# control_board.net
KiCad netlist of a schematic drawn in EAGLE
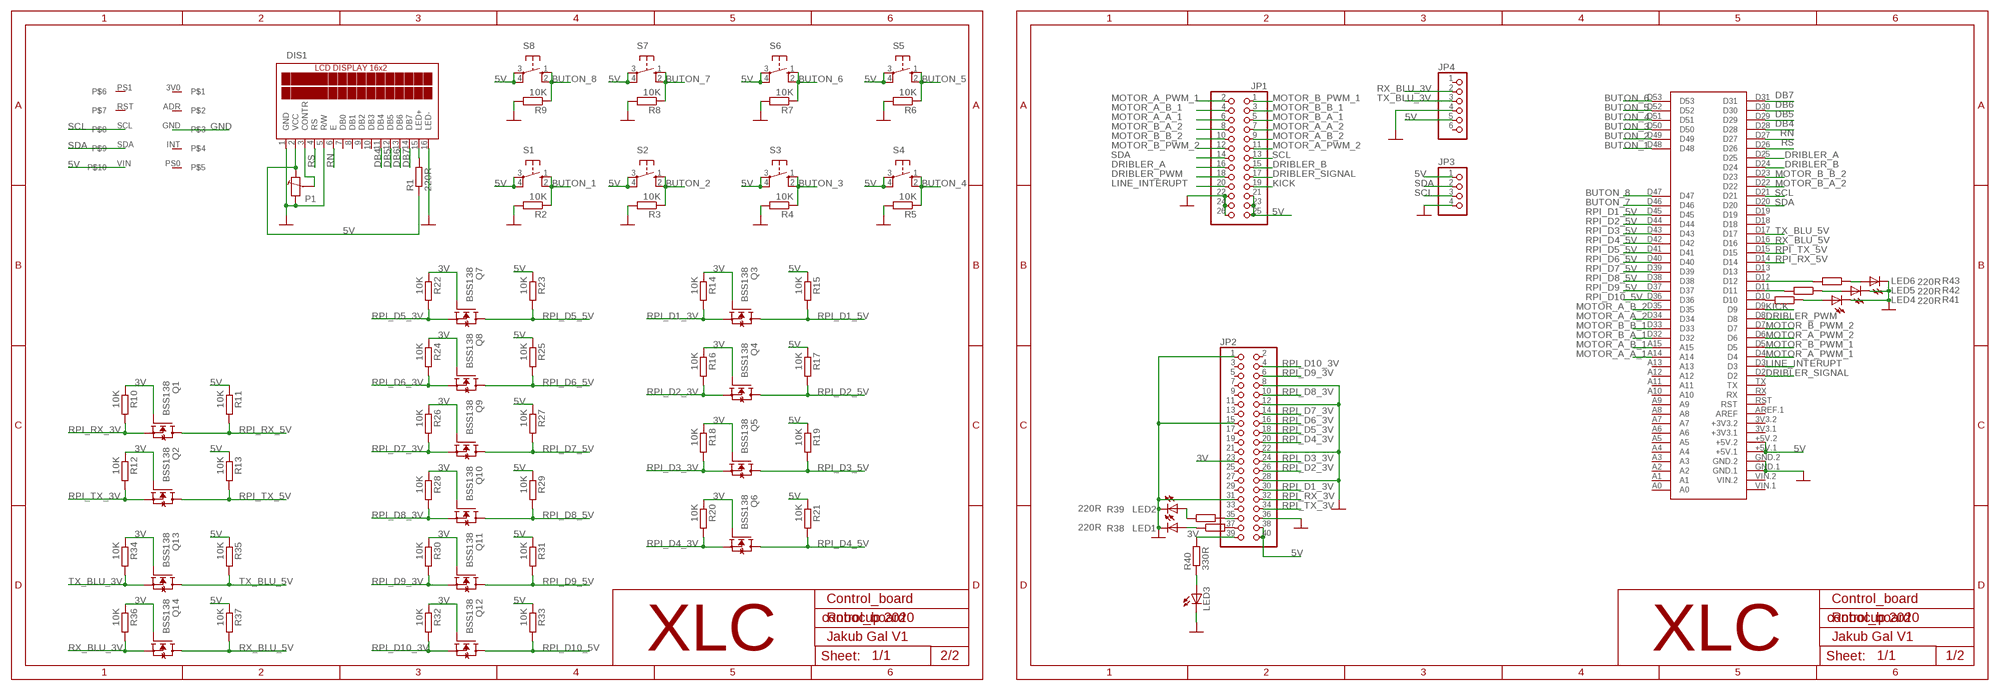
[diagram p0: schematic, sheet 1]

(export (version "E")
  (design (tool "Eeschema 10.0.6"))
  (components
    (comp (ref "DIS1")
      (value "LCD_DISPLEJ_16X2Z")
      (footprint "eagle-import:LCD_DISPLEJ_16X2")
      (libsource (lib "eagle-import") (part "LCD_DISPLEJ_16X2Z"))
    )
    (comp (ref "JP1")
      (value "PINHD-2X13_2.54")
      (footprint "eagle-import:2X13")
      (libsource (lib "eagle-import") (part "PINHD-2X13_2.54"))
    )
    (comp (ref "JP2")
      (value "PINHD-2X20_2.54")
      (footprint "eagle-import:2X20")
      (libsource (lib "eagle-import") (part "PINHD-2X20_2.54"))
    )
    (comp (ref "JP3")
      (value "PINHD-1X4_2.54")
      (footprint "eagle-import:1X04")
      (libsource (lib "eagle-import") (part "PINHD-1X4_2.54"))
    )
    (comp (ref "JP4")
      (value "PINHD-1X6_2.54")
      (footprint "eagle-import:1X06")
      (libsource (lib "eagle-import") (part "PINHD-1X6_2.54"))
    )
    (comp (ref "LED1")
      (value "LEDCHIPLED_0603")
      (footprint "eagle-import:CHIPLED_0603")
      (libsource (lib "eagle-import") (part "LEDCHIPLED_0603"))
    )
    (comp (ref "LED2")
      (value "LEDCHIPLED_0603")
      (footprint "eagle-import:CHIPLED_0603")
      (libsource (lib "eagle-import") (part "LEDCHIPLED_0603"))
    )
    (comp (ref "LED3")
      (value "LEDCHIPLED_0603")
      (footprint "eagle-import:CHIPLED_0603")
      (libsource (lib "eagle-import") (part "LEDCHIPLED_0603"))
    )
    (comp (ref "LED4")
      (value "LEDCHIPLED_0603")
      (footprint "eagle-import:CHIPLED_0603")
      (libsource (lib "eagle-import") (part "LEDCHIPLED_0603"))
    )
    (comp (ref "LED5")
      (value "LEDCHIPLED_0603")
      (footprint "eagle-import:CHIPLED_0603")
      (libsource (lib "eagle-import") (part "LEDCHIPLED_0603"))
    )
    (comp (ref "LED6")
      (value "LEDCHIPLED_0603")
      (footprint "eagle-import:CHIPLED_0603")
      (libsource (lib "eagle-import") (part "LEDCHIPLED_0603"))
    )
    (comp (ref "P1")
      (value "TRIMER-CA6V")
      (footprint "eagle-import:TP-CA6V")
      (libsource (lib "eagle-import") (part "TRIMER-CA6V"))
    )
    (comp (ref "Q1")
      (value "BSS138")
      (footprint "eagle-import:SOT23")
      (fields (field (name "MF") "Fairchild"))
      (libsource (lib "eagle-import") (part "BSS138"))
    )
    (comp (ref "Q2")
      (value "BSS138")
      (footprint "eagle-import:SOT23")
      (fields (field (name "MF") "Fairchild"))
      (libsource (lib "eagle-import") (part "BSS138"))
    )
    (comp (ref "Q3")
      (value "BSS138")
      (footprint "eagle-import:SOT23")
      (fields (field (name "MF") "Fairchild"))
      (libsource (lib "eagle-import") (part "BSS138"))
    )
    (comp (ref "Q4")
      (value "BSS138")
      (footprint "eagle-import:SOT23")
      (fields (field (name "MF") "Fairchild"))
      (libsource (lib "eagle-import") (part "BSS138"))
    )
    (comp (ref "Q5")
      (value "BSS138")
      (footprint "eagle-import:SOT23")
      (fields (field (name "MF") "Fairchild"))
      (libsource (lib "eagle-import") (part "BSS138"))
    )
    (comp (ref "Q6")
      (value "BSS138")
      (footprint "eagle-import:SOT23")
      (fields (field (name "MF") "Fairchild"))
      (libsource (lib "eagle-import") (part "BSS138"))
    )
    (comp (ref "Q7")
      (value "BSS138")
      (footprint "eagle-import:SOT23")
      (fields (field (name "MF") "Fairchild"))
      (libsource (lib "eagle-import") (part "BSS138"))
    )
    (comp (ref "Q8")
      (value "BSS138")
      (footprint "eagle-import:SOT23")
      (fields (field (name "MF") "Fairchild"))
      (libsource (lib "eagle-import") (part "BSS138"))
    )
    (comp (ref "Q9")
      (value "BSS138")
      (footprint "eagle-import:SOT23")
      (fields (field (name "MF") "Fairchild"))
      (libsource (lib "eagle-import") (part "BSS138"))
    )
    (comp (ref "Q10")
      (value "BSS138")
      (footprint "eagle-import:SOT23")
      (fields (field (name "MF") "Fairchild"))
      (libsource (lib "eagle-import") (part "BSS138"))
    )
    (comp (ref "Q11")
      (value "BSS138")
      (footprint "eagle-import:SOT23")
      (fields (field (name "MF") "Fairchild"))
      (libsource (lib "eagle-import") (part "BSS138"))
    )
    (comp (ref "Q12")
      (value "BSS138")
      (footprint "eagle-import:SOT23")
      (fields (field (name "MF") "Fairchild"))
      (libsource (lib "eagle-import") (part "BSS138"))
    )
    (comp (ref "Q13")
      (value "BSS138")
      (footprint "eagle-import:SOT23")
      (fields (field (name "MF") "Fairchild"))
      (libsource (lib "eagle-import") (part "BSS138"))
    )
    (comp (ref "Q14")
      (value "BSS138")
      (footprint "eagle-import:SOT23")
      (fields (field (name "MF") "Fairchild"))
      (libsource (lib "eagle-import") (part "BSS138"))
    )
    (comp (ref "R1")
      (value "220R")
      (footprint "eagle-import:R0603")
      (libsource (lib "eagle-import") (part "R-EU_R0603"))
    )
    (comp (ref "R2")
      (value "10K")
      (footprint "eagle-import:R0603")
      (libsource (lib "eagle-import") (part "R-EU_R0603"))
    )
    (comp (ref "R3")
      (value "10K")
      (footprint "eagle-import:R0603")
      (libsource (lib "eagle-import") (part "R-EU_R0603"))
    )
    (comp (ref "R4")
      (value "10K")
      (footprint "eagle-import:R0603")
      (libsource (lib "eagle-import") (part "R-EU_R0603"))
    )
    (comp (ref "R5")
      (value "10K")
      (footprint "eagle-import:R0603")
      (libsource (lib "eagle-import") (part "R-EU_R0603"))
    )
    (comp (ref "R6")
      (value "10K")
      (footprint "eagle-import:R0603")
      (libsource (lib "eagle-import") (part "R-EU_R0603"))
    )
    (comp (ref "R7")
      (value "10K")
      (footprint "eagle-import:R0603")
      (libsource (lib "eagle-import") (part "R-EU_R0603"))
    )
    (comp (ref "R8")
      (value "10K")
      (footprint "eagle-import:R0603")
      (libsource (lib "eagle-import") (part "R-EU_R0603"))
    )
    (comp (ref "R9")
      (value "10K")
      (footprint "eagle-import:R0603")
      (libsource (lib "eagle-import") (part "R-EU_R0603"))
    )
    (comp (ref "R10")
      (value "10K")
      (footprint "eagle-import:R0603")
      (libsource (lib "eagle-import") (part "R-EU_R0603"))
    )
    (comp (ref "R11")
      (value "10K")
      (footprint "eagle-import:R0603")
      (libsource (lib "eagle-import") (part "R-EU_R0603"))
    )
    (comp (ref "R12")
      (value "10K")
      (footprint "eagle-import:R0603")
      (libsource (lib "eagle-import") (part "R-EU_R0603"))
    )
    (comp (ref "R13")
      (value "10K")
      (footprint "eagle-import:R0603")
      (libsource (lib "eagle-import") (part "R-EU_R0603"))
    )
    (comp (ref "R14")
      (value "10K")
      (footprint "eagle-import:R0603")
      (libsource (lib "eagle-import") (part "R-EU_R0603"))
    )
    (comp (ref "R15")
      (value "10K")
      (footprint "eagle-import:R0603")
      (libsource (lib "eagle-import") (part "R-EU_R0603"))
    )
    (comp (ref "R16")
      (value "10K")
      (footprint "eagle-import:R0603")
      (libsource (lib "eagle-import") (part "R-EU_R0603"))
    )
    (comp (ref "R17")
      (value "10K")
      (footprint "eagle-import:R0603")
      (libsource (lib "eagle-import") (part "R-EU_R0603"))
    )
    (comp (ref "R18")
      (value "10K")
      (footprint "eagle-import:R0603")
      (libsource (lib "eagle-import") (part "R-EU_R0603"))
    )
    (comp (ref "R19")
      (value "10K")
      (footprint "eagle-import:R0603")
      (libsource (lib "eagle-import") (part "R-EU_R0603"))
    )
    (comp (ref "R20")
      (value "10K")
      (footprint "eagle-import:R0603")
      (libsource (lib "eagle-import") (part "R-EU_R0603"))
    )
    (comp (ref "R21")
      (value "10K")
      (footprint "eagle-import:R0603")
      (libsource (lib "eagle-import") (part "R-EU_R0603"))
    )
    (comp (ref "R22")
      (value "10K")
      (footprint "eagle-import:R0603")
      (libsource (lib "eagle-import") (part "R-EU_R0603"))
    )
    (comp (ref "R23")
      (value "10K")
      (footprint "eagle-import:R0603")
      (libsource (lib "eagle-import") (part "R-EU_R0603"))
    )
    (comp (ref "R24")
      (value "10K")
      (footprint "eagle-import:R0603")
      (libsource (lib "eagle-import") (part "R-EU_R0603"))
    )
    (comp (ref "R25")
      (value "10K")
      (footprint "eagle-import:R0603")
      (libsource (lib "eagle-import") (part "R-EU_R0603"))
    )
    (comp (ref "R26")
      (value "10K")
      (footprint "eagle-import:R0603")
      (libsource (lib "eagle-import") (part "R-EU_R0603"))
    )
    (comp (ref "R27")
      (value "10K")
      (footprint "eagle-import:R0603")
      (libsource (lib "eagle-import") (part "R-EU_R0603"))
    )
    (comp (ref "R28")
      (value "10K")
      (footprint "eagle-import:R0603")
      (libsource (lib "eagle-import") (part "R-EU_R0603"))
    )
    (comp (ref "R29")
      (value "10K")
      (footprint "eagle-import:R0603")
      (libsource (lib "eagle-import") (part "R-EU_R0603"))
    )
    (comp (ref "R30")
      (value "10K")
      (footprint "eagle-import:R0603")
      (libsource (lib "eagle-import") (part "R-EU_R0603"))
    )
    (comp (ref "R31")
      (value "10K")
      (footprint "eagle-import:R0603")
      (libsource (lib "eagle-import") (part "R-EU_R0603"))
    )
    (comp (ref "R32")
      (value "10K")
      (footprint "eagle-import:R0603")
      (libsource (lib "eagle-import") (part "R-EU_R0603"))
    )
    (comp (ref "R33")
      (value "10K")
      (footprint "eagle-import:R0603")
      (libsource (lib "eagle-import") (part "R-EU_R0603"))
    )
    (comp (ref "R34")
      (value "10K")
      (footprint "eagle-import:R0603")
      (libsource (lib "eagle-import") (part "R-EU_R0603"))
    )
    (comp (ref "R35")
      (value "10K")
      (footprint "eagle-import:R0603")
      (libsource (lib "eagle-import") (part "R-EU_R0603"))
    )
    (comp (ref "R36")
      (value "10K")
      (footprint "eagle-import:R0603")
      (libsource (lib "eagle-import") (part "R-EU_R0603"))
    )
    (comp (ref "R37")
      (value "10K")
      (footprint "eagle-import:R0603")
      (libsource (lib "eagle-import") (part "R-EU_R0603"))
    )
    (comp (ref "R38")
      (value "220R")
      (footprint "eagle-import:R0603")
      (libsource (lib "eagle-import") (part "R-EU_R0603"))
    )
    (comp (ref "R39")
      (value "220R")
      (footprint "eagle-import:R0603")
      (libsource (lib "eagle-import") (part "R-EU_R0603"))
    )
    (comp (ref "R40")
      (value "330R")
      (footprint "eagle-import:R0603")
      (libsource (lib "eagle-import") (part "R-EU_R0603"))
    )
    (comp (ref "R41")
      (value "220R")
      (footprint "eagle-import:R0603")
      (libsource (lib "eagle-import") (part "R-EU_R0603"))
    )
    (comp (ref "R42")
      (value "220R")
      (footprint "eagle-import:R0603")
      (libsource (lib "eagle-import") (part "R-EU_R0603"))
    )
    (comp (ref "R43")
      (value "220R")
      (footprint "eagle-import:R0603")
      (libsource (lib "eagle-import") (part "R-EU_R0603"))
    )
    (comp (ref "S1")
      (value "10-XX")
      (footprint "eagle-import:B3F-10XX")
      (fields (field (name "MPN") "B3F-1000"))
      (libsource (lib "eagle-import") (part "10-XX"))
    )
    (comp (ref "S2")
      (value "10-XX")
      (footprint "eagle-import:B3F-10XX")
      (fields (field (name "MPN") "B3F-1000"))
      (libsource (lib "eagle-import") (part "10-XX"))
    )
    (comp (ref "S3")
      (value "10-XX")
      (footprint "eagle-import:B3F-10XX")
      (fields (field (name "MPN") "B3F-1000"))
      (libsource (lib "eagle-import") (part "10-XX"))
    )
    (comp (ref "S4")
      (value "10-XX")
      (footprint "eagle-import:B3F-10XX")
      (fields (field (name "MPN") "B3F-1000"))
      (libsource (lib "eagle-import") (part "10-XX"))
    )
    (comp (ref "S5")
      (value "10-XX")
      (footprint "eagle-import:B3F-10XX")
      (fields (field (name "MPN") "B3F-1000"))
      (libsource (lib "eagle-import") (part "10-XX"))
    )
    (comp (ref "S6")
      (value "10-XX")
      (footprint "eagle-import:B3F-10XX")
      (fields (field (name "MPN") "B3F-1000"))
      (libsource (lib "eagle-import") (part "10-XX"))
    )
    (comp (ref "S7")
      (value "10-XX")
      (footprint "eagle-import:B3F-10XX")
      (fields (field (name "MPN") "B3F-1000"))
      (libsource (lib "eagle-import") (part "10-XX"))
    )
    (comp (ref "S8")
      (value "10-XX")
      (footprint "eagle-import:B3F-10XX")
      (fields (field (name "MPN") "B3F-1000"))
      (libsource (lib "eagle-import") (part "10-XX"))
    )
    (comp (ref "U$1")
      (value "MEGA2560_MIKRO")
      (footprint "eagle-import:MEGA2560_MIKRO")
      (libsource (lib "eagle-import") (part "MEGA2560_MIKRO"))
    )
    (comp (ref "U$2")
      (value "BNO055")
      (footprint "eagle-import:BNO005")
      (libsource (lib "eagle-import") (part "BNO055"))
    )
  )
  (nets
    (net (code "1") (name "/3V") (class "Default")
      (node (ref "JP2") (pin "23") (pinfunction "23_23") (pintype "passive"))
      (node (ref "JP2") (pin "39") (pinfunction "39_39") (pintype "passive"))
      (node (ref "Q1") (pin "1") (pinfunction "G_1") (pintype "passive"))
      (node (ref "Q10") (pin "1") (pinfunction "G_1") (pintype "passive"))
      (node (ref "Q11") (pin "1") (pinfunction "G_1") (pintype "passive"))
      (node (ref "Q12") (pin "1") (pinfunction "G_1") (pintype "passive"))
      (node (ref "Q13") (pin "1") (pinfunction "G_1") (pintype "passive"))
      (node (ref "Q14") (pin "1") (pinfunction "G_1") (pintype "passive"))
      (node (ref "Q2") (pin "1") (pinfunction "G_1") (pintype "passive"))
      (node (ref "Q3") (pin "1") (pinfunction "G_1") (pintype "passive"))
      (node (ref "Q4") (pin "1") (pinfunction "G_1") (pintype "passive"))
      (node (ref "Q5") (pin "1") (pinfunction "G_1") (pintype "passive"))
      (node (ref "Q6") (pin "1") (pinfunction "G_1") (pintype "passive"))
      (node (ref "Q7") (pin "1") (pinfunction "G_1") (pintype "passive"))
      (node (ref "Q8") (pin "1") (pinfunction "G_1") (pintype "passive"))
      (node (ref "Q9") (pin "1") (pinfunction "G_1") (pintype "passive"))
      (node (ref "R10") (pin "1") (pinfunction "1_1") (pintype "passive"))
      (node (ref "R12") (pin "1") (pinfunction "1_1") (pintype "passive"))
      (node (ref "R14") (pin "1") (pinfunction "1_1") (pintype "passive"))
      (node (ref "R16") (pin "1") (pinfunction "1_1") (pintype "passive"))
      (node (ref "R18") (pin "1") (pinfunction "1_1") (pintype "passive"))
      (node (ref "R20") (pin "1") (pinfunction "1_1") (pintype "passive"))
      (node (ref "R22") (pin "1") (pinfunction "1_1") (pintype "passive"))
      (node (ref "R24") (pin "1") (pinfunction "1_1") (pintype "passive"))
      (node (ref "R26") (pin "1") (pinfunction "1_1") (pintype "passive"))
      (node (ref "R28") (pin "1") (pinfunction "1_1") (pintype "passive"))
      (node (ref "R30") (pin "1") (pinfunction "1_1") (pintype "passive"))
      (node (ref "R32") (pin "1") (pinfunction "1_1") (pintype "passive"))
      (node (ref "R34") (pin "1") (pinfunction "1_1") (pintype "passive"))
      (node (ref "R36") (pin "1") (pinfunction "1_1") (pintype "passive"))
      (node (ref "R40") (pin "2") (pinfunction "2_2") (pintype "passive"))
    )
    (net (code "2") (name "/5V") (class "Default")
      (node (ref "DIS1") (pin "2") (pinfunction "VCC_2") (pintype "power_in"))
      (node (ref "JP1") (pin "21") (pinfunction "21_21") (pintype "passive"))
      (node (ref "JP1") (pin "23") (pinfunction "23_23") (pintype "passive"))
      (node (ref "JP1") (pin "25") (pinfunction "25_25") (pintype "passive"))
      (node (ref "JP2") (pin "38") (pinfunction "38_38") (pintype "passive"))
      (node (ref "JP2") (pin "40") (pinfunction "40_40") (pintype "passive"))
      (node (ref "JP3") (pin "1") (pinfunction "1_1") (pintype "passive"))
      (node (ref "JP4") (pin "5") (pinfunction "5_5") (pintype "passive"))
      (node (ref "P1") (pin "2") (pinfunction "2_2") (pintype "passive"))
      (node (ref "R1") (pin "1") (pinfunction "1_1") (pintype "passive"))
      (node (ref "R11") (pin "1") (pinfunction "1_1") (pintype "passive"))
      (node (ref "R13") (pin "1") (pinfunction "1_1") (pintype "passive"))
      (node (ref "R15") (pin "1") (pinfunction "1_1") (pintype "passive"))
      (node (ref "R17") (pin "1") (pinfunction "1_1") (pintype "passive"))
      (node (ref "R19") (pin "1") (pinfunction "1_1") (pintype "passive"))
      (node (ref "R21") (pin "1") (pinfunction "1_1") (pintype "passive"))
      (node (ref "R23") (pin "1") (pinfunction "1_1") (pintype "passive"))
      (node (ref "R25") (pin "1") (pinfunction "1_1") (pintype "passive"))
      (node (ref "R27") (pin "1") (pinfunction "1_1") (pintype "passive"))
      (node (ref "R29") (pin "1") (pinfunction "1_1") (pintype "passive"))
      (node (ref "R31") (pin "1") (pinfunction "1_1") (pintype "passive"))
      (node (ref "R33") (pin "1") (pinfunction "1_1") (pintype "passive"))
      (node (ref "R35") (pin "1") (pinfunction "1_1") (pintype "passive"))
      (node (ref "R37") (pin "1") (pinfunction "1_1") (pintype "passive"))
      (node (ref "S1") (pin "3") (pinfunction "P_3") (pintype "passive"))
      (node (ref "S1") (pin "4") (pinfunction "P1_4") (pintype "passive"))
      (node (ref "S2") (pin "3") (pinfunction "P_3") (pintype "passive"))
      (node (ref "S2") (pin "4") (pinfunction "P1_4") (pintype "passive"))
      (node (ref "S3") (pin "3") (pinfunction "P_3") (pintype "passive"))
      (node (ref "S3") (pin "4") (pinfunction "P1_4") (pintype "passive"))
      (node (ref "S4") (pin "3") (pinfunction "P_3") (pintype "passive"))
      (node (ref "S4") (pin "4") (pinfunction "P1_4") (pintype "passive"))
      (node (ref "S5") (pin "3") (pinfunction "P_3") (pintype "passive"))
      (node (ref "S5") (pin "4") (pinfunction "P1_4") (pintype "passive"))
      (node (ref "S6") (pin "3") (pinfunction "P_3") (pintype "passive"))
      (node (ref "S6") (pin "4") (pinfunction "P1_4") (pintype "passive"))
      (node (ref "S7") (pin "3") (pinfunction "P_3") (pintype "passive"))
      (node (ref "S7") (pin "4") (pinfunction "P1_4") (pintype "passive"))
      (node (ref "S8") (pin "3") (pinfunction "P_3") (pintype "passive"))
      (node (ref "S8") (pin "4") (pinfunction "P1_4") (pintype "passive"))
      (node (ref "U$1") (pin "+5V.1") (pinfunction "+5V.1_+5V.1") (pintype "bidirectional"))
      (node (ref "U$1") (pin "+5V.2") (pinfunction "+5V.2_+5V.2") (pintype "bidirectional"))
      (node (ref "U$2") (pin "VIN") (pinfunction "P$10_VIN") (pintype "bidirectional"))
    )
    (net (code "3") (name "/BUTON_1") (class "Default")
      (node (ref "R2") (pin "1") (pinfunction "1_1") (pintype "passive"))
      (node (ref "S1") (pin "1") (pinfunction "S_1") (pintype "passive"))
      (node (ref "S1") (pin "2") (pinfunction "S1_2") (pintype "passive"))
      (node (ref "U$1") (pin "D48") (pinfunction "D48_D48") (pintype "bidirectional"))
    )
    (net (code "4") (name "/BUTON_2") (class "Default")
      (node (ref "R3") (pin "1") (pinfunction "1_1") (pintype "passive"))
      (node (ref "S2") (pin "1") (pinfunction "S_1") (pintype "passive"))
      (node (ref "S2") (pin "2") (pinfunction "S1_2") (pintype "passive"))
      (node (ref "U$1") (pin "D49") (pinfunction "D49_D49") (pintype "bidirectional"))
    )
    (net (code "5") (name "/BUTON_3") (class "Default")
      (node (ref "R4") (pin "1") (pinfunction "1_1") (pintype "passive"))
      (node (ref "S3") (pin "1") (pinfunction "S_1") (pintype "passive"))
      (node (ref "S3") (pin "2") (pinfunction "S1_2") (pintype "passive"))
      (node (ref "U$1") (pin "D50") (pinfunction "D50_D50") (pintype "bidirectional"))
    )
    (net (code "6") (name "/BUTON_4") (class "Default")
      (node (ref "R5") (pin "1") (pinfunction "1_1") (pintype "passive"))
      (node (ref "S4") (pin "1") (pinfunction "S_1") (pintype "passive"))
      (node (ref "S4") (pin "2") (pinfunction "S1_2") (pintype "passive"))
      (node (ref "U$1") (pin "D51") (pinfunction "D51_D51") (pintype "bidirectional"))
    )
    (net (code "7") (name "/BUTON_5") (class "Default")
      (node (ref "R6") (pin "1") (pinfunction "1_1") (pintype "passive"))
      (node (ref "S5") (pin "1") (pinfunction "S_1") (pintype "passive"))
      (node (ref "S5") (pin "2") (pinfunction "S1_2") (pintype "passive"))
      (node (ref "U$1") (pin "D52") (pinfunction "D52_D52") (pintype "bidirectional"))
    )
    (net (code "8") (name "/BUTON_6") (class "Default")
      (node (ref "R7") (pin "1") (pinfunction "1_1") (pintype "passive"))
      (node (ref "S6") (pin "1") (pinfunction "S_1") (pintype "passive"))
      (node (ref "S6") (pin "2") (pinfunction "S1_2") (pintype "passive"))
      (node (ref "U$1") (pin "D53") (pinfunction "D53_D53") (pintype "bidirectional"))
    )
    (net (code "9") (name "/BUTON_7") (class "Default")
      (node (ref "R8") (pin "1") (pinfunction "1_1") (pintype "passive"))
      (node (ref "S7") (pin "1") (pinfunction "S_1") (pintype "passive"))
      (node (ref "S7") (pin "2") (pinfunction "S1_2") (pintype "passive"))
      (node (ref "U$1") (pin "D46") (pinfunction "D46_D46") (pintype "bidirectional"))
    )
    (net (code "10") (name "/BUTON_8") (class "Default")
      (node (ref "R9") (pin "1") (pinfunction "1_1") (pintype "passive"))
      (node (ref "S8") (pin "1") (pinfunction "S_1") (pintype "passive"))
      (node (ref "S8") (pin "2") (pinfunction "S1_2") (pintype "passive"))
      (node (ref "U$1") (pin "D47") (pinfunction "D47_D47") (pintype "bidirectional"))
    )
    (net (code "11") (name "/DB4") (class "Default")
      (node (ref "DIS1") (pin "11") (pinfunction "DB4_11") (pintype "bidirectional"))
      (node (ref "U$1") (pin "D28") (pinfunction "D28_D28") (pintype "bidirectional"))
    )
    (net (code "12") (name "/DB5") (class "Default")
      (node (ref "DIS1") (pin "12") (pinfunction "DB5_12") (pintype "bidirectional"))
      (node (ref "U$1") (pin "D29") (pinfunction "D29_D29") (pintype "bidirectional"))
    )
    (net (code "13") (name "/DB6") (class "Default")
      (node (ref "DIS1") (pin "13") (pinfunction "DB6_13") (pintype "bidirectional"))
      (node (ref "U$1") (pin "D30") (pinfunction "D30_D30") (pintype "bidirectional"))
    )
    (net (code "14") (name "/DB7") (class "Default")
      (node (ref "DIS1") (pin "14") (pinfunction "DB7_14") (pintype "bidirectional"))
      (node (ref "U$1") (pin "D31") (pinfunction "D31_D31") (pintype "bidirectional"))
    )
    (net (code "15") (name "/DRIBLER_A") (class "Default")
      (node (ref "JP1") (pin "16") (pinfunction "16_16") (pintype "passive"))
      (node (ref "U$1") (pin "D25") (pinfunction "D25_D25") (pintype "bidirectional"))
    )
    (net (code "16") (name "/DRIBLER_B") (class "Default")
      (node (ref "JP1") (pin "15") (pinfunction "15_15") (pintype "passive"))
      (node (ref "U$1") (pin "D24") (pinfunction "D24_D24") (pintype "bidirectional"))
    )
    (net (code "17") (name "/DRIBLER_PWM") (class "Default")
      (node (ref "JP1") (pin "18") (pinfunction "18_18") (pintype "passive"))
      (node (ref "U$1") (pin "D8") (pinfunction "D8_D8") (pintype "bidirectional"))
    )
    (net (code "18") (name "/DRIBLER_SIGNAL") (class "Default")
      (node (ref "JP1") (pin "17") (pinfunction "17_17") (pintype "passive"))
      (node (ref "U$1") (pin "D2") (pinfunction "D2_D2") (pintype "bidirectional"))
    )
    (net (code "19") (name "/KICK") (class "Default")
      (node (ref "JP1") (pin "19") (pinfunction "19_19") (pintype "passive"))
      (node (ref "U$1") (pin "D9") (pinfunction "D9_D9") (pintype "bidirectional"))
    )
    (net (code "20") (name "/LINE_INTERUPT") (class "Default")
      (node (ref "JP1") (pin "20") (pinfunction "20_20") (pintype "passive"))
      (node (ref "U$1") (pin "D3") (pinfunction "D3_D3") (pintype "bidirectional"))
    )
    (net (code "21") (name "/MOTOR_A_A_1") (class "Default")
      (node (ref "JP1") (pin "6") (pinfunction "6_6") (pintype "passive"))
      (node (ref "U$1") (pin "A14") (pinfunction "A14_A14") (pintype "bidirectional"))
    )
    (net (code "22") (name "/MOTOR_A_A_2") (class "Default")
      (node (ref "JP1") (pin "7") (pinfunction "7_7") (pintype "passive"))
      (node (ref "U$1") (pin "D34") (pinfunction "D34_D34") (pintype "bidirectional"))
    )
    (net (code "23") (name "/MOTOR_A_B_1") (class "Default")
      (node (ref "JP1") (pin "4") (pinfunction "4_4") (pintype "passive"))
      (node (ref "U$1") (pin "A15") (pinfunction "A15_A15") (pintype "bidirectional"))
    )
    (net (code "24") (name "/MOTOR_A_B_2") (class "Default")
      (node (ref "JP1") (pin "9") (pinfunction "9_9") (pintype "passive"))
      (node (ref "U$1") (pin "D35") (pinfunction "D35_D35") (pintype "bidirectional"))
    )
    (net (code "25") (name "/MOTOR_A_PWM_1") (class "Default")
      (node (ref "JP1") (pin "2") (pinfunction "2_2") (pintype "passive"))
      (node (ref "U$1") (pin "D4") (pinfunction "D4_D4") (pintype "bidirectional"))
    )
    (net (code "26") (name "/MOTOR_A_PWM_2") (class "Default")
      (node (ref "JP1") (pin "11") (pinfunction "11_11") (pintype "passive"))
      (node (ref "U$1") (pin "D6") (pinfunction "D6_D6") (pintype "bidirectional"))
    )
    (net (code "27") (name "/MOTOR_B_A_1") (class "Default")
      (node (ref "JP1") (pin "5") (pinfunction "5_5") (pintype "passive"))
      (node (ref "U$1") (pin "D32") (pinfunction "D32_D32") (pintype "bidirectional"))
    )
    (net (code "28") (name "/MOTOR_B_A_2") (class "Default")
      (node (ref "JP1") (pin "8") (pinfunction "8_8") (pintype "passive"))
      (node (ref "U$1") (pin "D22") (pinfunction "D22_D22") (pintype "bidirectional"))
    )
    (net (code "29") (name "/MOTOR_B_B_1") (class "Default")
      (node (ref "JP1") (pin "3") (pinfunction "3_3") (pintype "passive"))
      (node (ref "U$1") (pin "D33") (pinfunction "D33_D33") (pintype "bidirectional"))
    )
    (net (code "30") (name "/MOTOR_B_B_2") (class "Default")
      (node (ref "JP1") (pin "10") (pinfunction "10_10") (pintype "passive"))
      (node (ref "U$1") (pin "D23") (pinfunction "D23_D23") (pintype "bidirectional"))
    )
    (net (code "31") (name "/MOTOR_B_PWM_1") (class "Default")
      (node (ref "JP1") (pin "1") (pinfunction "1_1") (pintype "passive"))
      (node (ref "U$1") (pin "D5") (pinfunction "D5_D5") (pintype "bidirectional"))
    )
    (net (code "32") (name "/MOTOR_B_PWM_2") (class "Default")
      (node (ref "JP1") (pin "12") (pinfunction "12_12") (pintype "passive"))
      (node (ref "U$1") (pin "D7") (pinfunction "D7_D7") (pintype "bidirectional"))
    )
    (net (code "33") (name "/RN") (class "Default")
      (node (ref "DIS1") (pin "6") (pinfunction "E_6") (pintype "input"))
      (node (ref "U$1") (pin "D27") (pinfunction "D27_D27") (pintype "bidirectional"))
    )
    (net (code "34") (name "/RPI_D1_3V") (class "Default")
      (node (ref "JP2") (pin "30") (pinfunction "30_30") (pintype "passive"))
      (node (ref "Q3") (pin "2") (pinfunction "S_2") (pintype "passive"))
      (node (ref "R14") (pin "2") (pinfunction "2_2") (pintype "passive"))
    )
    (net (code "35") (name "/RPI_D1_5V") (class "Default")
      (node (ref "Q3") (pin "3") (pinfunction "D_3") (pintype "passive"))
      (node (ref "R15") (pin "2") (pinfunction "2_2") (pintype "passive"))
      (node (ref "U$1") (pin "D45") (pinfunction "D45_D45") (pintype "bidirectional"))
    )
    (net (code "36") (name "/RPI_D2_3V") (class "Default")
      (node (ref "JP2") (pin "26") (pinfunction "26_26") (pintype "passive"))
      (node (ref "Q4") (pin "2") (pinfunction "S_2") (pintype "passive"))
      (node (ref "R16") (pin "2") (pinfunction "2_2") (pintype "passive"))
    )
    (net (code "37") (name "/RPI_D2_5V") (class "Default")
      (node (ref "Q4") (pin "3") (pinfunction "D_3") (pintype "passive"))
      (node (ref "R17") (pin "2") (pinfunction "2_2") (pintype "passive"))
      (node (ref "U$1") (pin "D44") (pinfunction "D44_D44") (pintype "bidirectional"))
    )
    (net (code "38") (name "/RPI_D3_3V") (class "Default")
      (node (ref "JP2") (pin "24") (pinfunction "24_24") (pintype "passive"))
      (node (ref "Q5") (pin "2") (pinfunction "S_2") (pintype "passive"))
      (node (ref "R18") (pin "2") (pinfunction "2_2") (pintype "passive"))
    )
    (net (code "39") (name "/RPI_D3_5V") (class "Default")
      (node (ref "Q5") (pin "3") (pinfunction "D_3") (pintype "passive"))
      (node (ref "R19") (pin "2") (pinfunction "2_2") (pintype "passive"))
      (node (ref "U$1") (pin "D43") (pinfunction "D43_D43") (pintype "bidirectional"))
    )
    (net (code "40") (name "/RPI_D4_3V") (class "Default")
      (node (ref "JP2") (pin "20") (pinfunction "20_20") (pintype "passive"))
      (node (ref "Q6") (pin "2") (pinfunction "S_2") (pintype "passive"))
      (node (ref "R20") (pin "2") (pinfunction "2_2") (pintype "passive"))
    )
    (net (code "41") (name "/RPI_D4_5V") (class "Default")
      (node (ref "Q6") (pin "3") (pinfunction "D_3") (pintype "passive"))
      (node (ref "R21") (pin "2") (pinfunction "2_2") (pintype "passive"))
      (node (ref "U$1") (pin "D42") (pinfunction "D42_D42") (pintype "bidirectional"))
    )
    (net (code "42") (name "/RPI_D5_3V") (class "Default")
      (node (ref "JP2") (pin "18") (pinfunction "18_18") (pintype "passive"))
      (node (ref "Q7") (pin "2") (pinfunction "S_2") (pintype "passive"))
      (node (ref "R22") (pin "2") (pinfunction "2_2") (pintype "passive"))
    )
    (net (code "43") (name "/RPI_D5_5V") (class "Default")
      (node (ref "Q7") (pin "3") (pinfunction "D_3") (pintype "passive"))
      (node (ref "R23") (pin "2") (pinfunction "2_2") (pintype "passive"))
      (node (ref "U$1") (pin "D41") (pinfunction "D41_D41") (pintype "bidirectional"))
    )
    (net (code "44") (name "/RPI_D6_3V") (class "Default")
      (node (ref "JP2") (pin "16") (pinfunction "16_16") (pintype "passive"))
      (node (ref "Q8") (pin "2") (pinfunction "S_2") (pintype "passive"))
      (node (ref "R24") (pin "2") (pinfunction "2_2") (pintype "passive"))
    )
    (net (code "45") (name "/RPI_D6_5V") (class "Default")
      (node (ref "Q8") (pin "3") (pinfunction "D_3") (pintype "passive"))
      (node (ref "R25") (pin "2") (pinfunction "2_2") (pintype "passive"))
      (node (ref "U$1") (pin "D40") (pinfunction "D40_D40") (pintype "bidirectional"))
    )
    (net (code "46") (name "/RPI_D7_3V") (class "Default")
      (node (ref "JP2") (pin "14") (pinfunction "14_14") (pintype "passive"))
      (node (ref "Q9") (pin "2") (pinfunction "S_2") (pintype "passive"))
      (node (ref "R26") (pin "2") (pinfunction "2_2") (pintype "passive"))
    )
    (net (code "47") (name "/RPI_D7_5V") (class "Default")
      (node (ref "Q9") (pin "3") (pinfunction "D_3") (pintype "passive"))
      (node (ref "R27") (pin "2") (pinfunction "2_2") (pintype "passive"))
      (node (ref "U$1") (pin "D39") (pinfunction "D39_D39") (pintype "bidirectional"))
    )
    (net (code "48") (name "/RPI_D8_3V") (class "Default")
      (node (ref "JP2") (pin "10") (pinfunction "10_10") (pintype "passive"))
      (node (ref "Q10") (pin "2") (pinfunction "S_2") (pintype "passive"))
      (node (ref "R28") (pin "2") (pinfunction "2_2") (pintype "passive"))
    )
    (net (code "49") (name "/RPI_D8_5V") (class "Default")
      (node (ref "Q10") (pin "3") (pinfunction "D_3") (pintype "passive"))
      (node (ref "R29") (pin "2") (pinfunction "2_2") (pintype "passive"))
      (node (ref "U$1") (pin "D38") (pinfunction "D38_D38") (pintype "bidirectional"))
    )
    (net (code "50") (name "/RPI_D9_3V") (class "Default")
      (node (ref "JP2") (pin "6") (pinfunction "6_6") (pintype "passive"))
      (node (ref "Q11") (pin "2") (pinfunction "S_2") (pintype "passive"))
      (node (ref "R30") (pin "2") (pinfunction "2_2") (pintype "passive"))
    )
    (net (code "51") (name "/RPI_D9_5V") (class "Default")
      (node (ref "Q11") (pin "3") (pinfunction "D_3") (pintype "passive"))
      (node (ref "R31") (pin "2") (pinfunction "2_2") (pintype "passive"))
      (node (ref "U$1") (pin "D37") (pinfunction "D37_D37") (pintype "bidirectional"))
    )
    (net (code "52") (name "/RPI_D10_3V") (class "Default")
      (node (ref "JP2") (pin "4") (pinfunction "4_4") (pintype "passive"))
      (node (ref "Q12") (pin "2") (pinfunction "S_2") (pintype "passive"))
      (node (ref "R32") (pin "2") (pinfunction "2_2") (pintype "passive"))
    )
    (net (code "53") (name "/RPI_D10_5V") (class "Default")
      (node (ref "Q12") (pin "3") (pinfunction "D_3") (pintype "passive"))
      (node (ref "R33") (pin "2") (pinfunction "2_2") (pintype "passive"))
      (node (ref "U$1") (pin "D36") (pinfunction "D36_D36") (pintype "bidirectional"))
    )
    (net (code "54") (name "/RPI_RX_3V") (class "Default")
      (node (ref "JP2") (pin "32") (pinfunction "32_32") (pintype "passive"))
      (node (ref "Q1") (pin "2") (pinfunction "S_2") (pintype "passive"))
      (node (ref "R10") (pin "2") (pinfunction "2_2") (pintype "passive"))
    )
    (net (code "55") (name "/RPI_RX_5V") (class "Default")
      (node (ref "Q1") (pin "3") (pinfunction "D_3") (pintype "passive"))
      (node (ref "R11") (pin "2") (pinfunction "2_2") (pintype "passive"))
      (node (ref "U$1") (pin "D14") (pinfunction "D14_D14") (pintype "bidirectional"))
    )
    (net (code "56") (name "/RPI_TX_3V") (class "Default")
      (node (ref "JP2") (pin "34") (pinfunction "34_34") (pintype "passive"))
      (node (ref "Q2") (pin "2") (pinfunction "S_2") (pintype "passive"))
      (node (ref "R12") (pin "2") (pinfunction "2_2") (pintype "passive"))
    )
    (net (code "57") (name "/RPI_TX_5V") (class "Default")
      (node (ref "Q2") (pin "3") (pinfunction "D_3") (pintype "passive"))
      (node (ref "R13") (pin "2") (pinfunction "2_2") (pintype "passive"))
      (node (ref "U$1") (pin "D15") (pinfunction "D15_D15") (pintype "bidirectional"))
    )
    (net (code "58") (name "/RS") (class "Default")
      (node (ref "DIS1") (pin "4") (pinfunction "RS_4") (pintype "input"))
      (node (ref "U$1") (pin "D26") (pinfunction "D26_D26") (pintype "bidirectional"))
    )
    (net (code "59") (name "/RX_BLU_3V") (class "Default")
      (node (ref "JP4") (pin "2") (pinfunction "2_2") (pintype "passive"))
      (node (ref "Q14") (pin "2") (pinfunction "S_2") (pintype "passive"))
      (node (ref "R36") (pin "2") (pinfunction "2_2") (pintype "passive"))
    )
    (net (code "60") (name "/RX_BLU_5V") (class "Default")
      (node (ref "Q14") (pin "3") (pinfunction "D_3") (pintype "passive"))
      (node (ref "R37") (pin "2") (pinfunction "2_2") (pintype "passive"))
      (node (ref "U$1") (pin "D16") (pinfunction "D16_D16") (pintype "bidirectional"))
    )
    (net (code "61") (name "/SCL") (class "Default")
      (node (ref "JP1") (pin "13") (pinfunction "13_13") (pintype "passive"))
      (node (ref "JP3") (pin "3") (pinfunction "3_3") (pintype "passive"))
      (node (ref "U$1") (pin "D21") (pinfunction "D21_D21") (pintype "bidirectional"))
      (node (ref "U$2") (pin "SCL") (pinfunction "P$8_SCL") (pintype "bidirectional"))
    )
    (net (code "62") (name "/SDA") (class "Default")
      (node (ref "JP1") (pin "14") (pinfunction "14_14") (pintype "passive"))
      (node (ref "JP3") (pin "2") (pinfunction "2_2") (pintype "passive"))
      (node (ref "U$1") (pin "D20") (pinfunction "D20_D20") (pintype "bidirectional"))
      (node (ref "U$2") (pin "SDA") (pinfunction "P$9_SDA") (pintype "bidirectional"))
    )
    (net (code "63") (name "/TX_BLU_3V") (class "Default")
      (node (ref "JP4") (pin "3") (pinfunction "3_3") (pintype "passive"))
      (node (ref "Q13") (pin "2") (pinfunction "S_2") (pintype "passive"))
      (node (ref "R34") (pin "2") (pinfunction "2_2") (pintype "passive"))
    )
    (net (code "64") (name "/TX_BLU_5V") (class "Default")
      (node (ref "Q13") (pin "3") (pinfunction "D_3") (pintype "passive"))
      (node (ref "R35") (pin "2") (pinfunction "2_2") (pintype "passive"))
      (node (ref "U$1") (pin "D17") (pinfunction "D17_D17") (pintype "bidirectional"))
    )
    (net (code "65") (name "GND") (class "Default")
      (node (ref "DIS1") (pin "1") (pinfunction "GND_1") (pintype "power_in"))
      (node (ref "DIS1") (pin "16") (pinfunction "LED-_16") (pintype "passive"))
      (node (ref "DIS1") (pin "5") (pinfunction "R/W_5") (pintype "input"))
      (node (ref "JP1") (pin "22") (pinfunction "22_22") (pintype "passive"))
      (node (ref "JP1") (pin "24") (pinfunction "24_24") (pintype "passive"))
      (node (ref "JP1") (pin "26") (pinfunction "26_26") (pintype "passive"))
      (node (ref "JP2") (pin "1") (pinfunction "1_1") (pintype "passive"))
      (node (ref "JP2") (pin "12") (pinfunction "12_12") (pintype "passive"))
      (node (ref "JP2") (pin "15") (pinfunction "15_15") (pintype "passive"))
      (node (ref "JP2") (pin "22") (pinfunction "22_22") (pintype "passive"))
      (node (ref "JP2") (pin "28") (pinfunction "28_28") (pintype "passive"))
      (node (ref "JP2") (pin "31") (pinfunction "31_31") (pintype "passive"))
      (node (ref "JP2") (pin "36") (pinfunction "36_36") (pintype "passive"))
      (node (ref "JP2") (pin "8") (pinfunction "8_8") (pintype "passive"))
      (node (ref "JP3") (pin "4") (pinfunction "4_4") (pintype "passive"))
      (node (ref "JP4") (pin "4") (pinfunction "4_4") (pintype "passive"))
      (node (ref "LED1") (pin "C") (pinfunction "C_C") (pintype "passive"))
      (node (ref "LED2") (pin "C") (pinfunction "C_C") (pintype "passive"))
      (node (ref "LED3") (pin "C") (pinfunction "C_C") (pintype "passive"))
      (node (ref "LED4") (pin "C") (pinfunction "C_C") (pintype "passive"))
      (node (ref "LED5") (pin "C") (pinfunction "C_C") (pintype "passive"))
      (node (ref "LED6") (pin "C") (pinfunction "C_C") (pintype "passive"))
      (node (ref "P1") (pin "1") (pinfunction "1_1") (pintype "passive"))
      (node (ref "R2") (pin "2") (pinfunction "2_2") (pintype "passive"))
      (node (ref "R3") (pin "2") (pinfunction "2_2") (pintype "passive"))
      (node (ref "R4") (pin "2") (pinfunction "2_2") (pintype "passive"))
      (node (ref "R5") (pin "2") (pinfunction "2_2") (pintype "passive"))
      (node (ref "R6") (pin "2") (pinfunction "2_2") (pintype "passive"))
      (node (ref "R7") (pin "2") (pinfunction "2_2") (pintype "passive"))
      (node (ref "R8") (pin "2") (pinfunction "2_2") (pintype "passive"))
      (node (ref "R9") (pin "2") (pinfunction "2_2") (pintype "passive"))
      (node (ref "U$1") (pin "GND.1") (pinfunction "GND.1_GND.1") (pintype "bidirectional"))
      (node (ref "U$1") (pin "GND.2") (pinfunction "GND.2_GND.2") (pintype "bidirectional"))
      (node (ref "U$2") (pin "GND") (pinfunction "P$3_GND") (pintype "bidirectional"))
    )
    (net (code "66") (name "Net-(DIS1-CONTR)") (class "Default")
      (node (ref "DIS1") (pin "3") (pinfunction "CONTR_3") (pintype "input"))
      (node (ref "P1") (pin "BEZ") (pinfunction "BEZ_BEZ") (pintype "passive"))
    )
    (net (code "67") (name "Net-(DIS1-LED+)") (class "Default")
      (node (ref "DIS1") (pin "15") (pinfunction "LED+_15") (pintype "passive"))
      (node (ref "R1") (pin "2") (pinfunction "2_2") (pintype "passive"))
    )
    (net (code "68") (name "Net-(JP2-Pad35)") (class "Default")
      (node (ref "JP2") (pin "35") (pinfunction "35_35") (pintype "passive"))
      (node (ref "R39") (pin "2") (pinfunction "2_2") (pintype "passive"))
    )
    (net (code "69") (name "Net-(JP2-Pad37)") (class "Default")
      (node (ref "JP2") (pin "37") (pinfunction "37_37") (pintype "passive"))
      (node (ref "R38") (pin "2") (pinfunction "2_2") (pintype "passive"))
    )
    (net (code "70") (name "Net-(LED1-PadA)") (class "Default")
      (node (ref "LED1") (pin "A") (pinfunction "A_A") (pintype "passive"))
      (node (ref "R38") (pin "1") (pinfunction "1_1") (pintype "passive"))
    )
    (net (code "71") (name "Net-(LED2-PadA)") (class "Default")
      (node (ref "LED2") (pin "A") (pinfunction "A_A") (pintype "passive"))
      (node (ref "R39") (pin "1") (pinfunction "1_1") (pintype "passive"))
    )
    (net (code "72") (name "Net-(LED3-PadA)") (class "Default")
      (node (ref "LED3") (pin "A") (pinfunction "A_A") (pintype "passive"))
      (node (ref "R40") (pin "1") (pinfunction "1_1") (pintype "passive"))
    )
    (net (code "73") (name "Net-(LED4-PadA)") (class "Default")
      (node (ref "LED4") (pin "A") (pinfunction "A_A") (pintype "passive"))
      (node (ref "R41") (pin "1") (pinfunction "1_1") (pintype "passive"))
    )
    (net (code "74") (name "Net-(LED5-PadA)") (class "Default")
      (node (ref "LED5") (pin "A") (pinfunction "A_A") (pintype "passive"))
      (node (ref "R42") (pin "1") (pinfunction "1_1") (pintype "passive"))
    )
    (net (code "75") (name "Net-(LED6-PadA)") (class "Default")
      (node (ref "LED6") (pin "A") (pinfunction "A_A") (pintype "passive"))
      (node (ref "R43") (pin "1") (pinfunction "1_1") (pintype "passive"))
    )
    (net (code "76") (name "Net-(R41-Pad2)") (class "Default")
      (node (ref "R41") (pin "2") (pinfunction "2_2") (pintype "passive"))
      (node (ref "U$1") (pin "D10") (pinfunction "D10_D10") (pintype "bidirectional"))
    )
    (net (code "77") (name "Net-(R42-Pad2)") (class "Default")
      (node (ref "R42") (pin "2") (pinfunction "2_2") (pintype "passive"))
      (node (ref "U$1") (pin "D11") (pinfunction "D11_D11") (pintype "bidirectional"))
    )
    (net (code "78") (name "Net-(R43-Pad2)") (class "Default")
      (node (ref "R43") (pin "2") (pinfunction "2_2") (pintype "passive"))
      (node (ref "U$1") (pin "D12") (pinfunction "D12_D12") (pintype "bidirectional"))
    )
    (net (code "79") (name "unconnected-(DIS1-DB0-Pad7)") (class "Default")
      (node (ref "DIS1") (pin "7") (pinfunction "DB0_7") (pintype "bidirectional"))
    )
    (net (code "80") (name "unconnected-(DIS1-DB1-Pad8)") (class "Default")
      (node (ref "DIS1") (pin "8") (pinfunction "DB1_8") (pintype "bidirectional"))
    )
    (net (code "81") (name "unconnected-(DIS1-DB2-Pad9)") (class "Default")
      (node (ref "DIS1") (pin "9") (pinfunction "DB2_9") (pintype "bidirectional"))
    )
    (net (code "82") (name "unconnected-(DIS1-DB3-Pad10)") (class "Default")
      (node (ref "DIS1") (pin "10") (pinfunction "DB3_10") (pintype "bidirectional"))
    )
    (net (code "83") (name "unconnected-(JP2-Pad2)") (class "Default")
      (node (ref "JP2") (pin "2") (pinfunction "2_2") (pintype "passive"))
    )
    (net (code "84") (name "unconnected-(JP2-Pad3)") (class "Default")
      (node (ref "JP2") (pin "3") (pinfunction "3_3") (pintype "passive"))
    )
    (net (code "85") (name "unconnected-(JP2-Pad5)") (class "Default")
      (node (ref "JP2") (pin "5") (pinfunction "5_5") (pintype "passive"))
    )
    (net (code "86") (name "unconnected-(JP2-Pad7)") (class "Default")
      (node (ref "JP2") (pin "7") (pinfunction "7_7") (pintype "passive"))
    )
    (net (code "87") (name "unconnected-(JP2-Pad9)") (class "Default")
      (node (ref "JP2") (pin "9") (pinfunction "9_9") (pintype "passive"))
    )
    (net (code "88") (name "unconnected-(JP2-Pad11)") (class "Default")
      (node (ref "JP2") (pin "11") (pinfunction "11_11") (pintype "passive"))
    )
    (net (code "89") (name "unconnected-(JP2-Pad13)") (class "Default")
      (node (ref "JP2") (pin "13") (pinfunction "13_13") (pintype "passive"))
    )
    (net (code "90") (name "unconnected-(JP2-Pad17)") (class "Default")
      (node (ref "JP2") (pin "17") (pinfunction "17_17") (pintype "passive"))
    )
    (net (code "91") (name "unconnected-(JP2-Pad19)") (class "Default")
      (node (ref "JP2") (pin "19") (pinfunction "19_19") (pintype "passive"))
    )
    (net (code "92") (name "unconnected-(JP2-Pad21)") (class "Default")
      (node (ref "JP2") (pin "21") (pinfunction "21_21") (pintype "passive"))
    )
    (net (code "93") (name "unconnected-(JP2-Pad25)") (class "Default")
      (node (ref "JP2") (pin "25") (pinfunction "25_25") (pintype "passive"))
    )
    (net (code "94") (name "unconnected-(JP2-Pad27)") (class "Default")
      (node (ref "JP2") (pin "27") (pinfunction "27_27") (pintype "passive"))
    )
    (net (code "95") (name "unconnected-(JP2-Pad29)") (class "Default")
      (node (ref "JP2") (pin "29") (pinfunction "29_29") (pintype "passive"))
    )
    (net (code "96") (name "unconnected-(JP2-Pad33)") (class "Default")
      (node (ref "JP2") (pin "33") (pinfunction "33_33") (pintype "passive"))
    )
    (net (code "97") (name "unconnected-(JP4-Pad1)") (class "Default")
      (node (ref "JP4") (pin "1") (pinfunction "1_1") (pintype "passive"))
    )
    (net (code "98") (name "unconnected-(JP4-Pad6)") (class "Default")
      (node (ref "JP4") (pin "6") (pinfunction "6_6") (pintype "passive"))
    )
    (net (code "99") (name "unconnected-(U$1-+3V3.1-Pad3V3.1)") (class "Default")
      (node (ref "U$1") (pin "3V3.1") (pinfunction "+3V3.1_3V3.1") (pintype "bidirectional"))
    )
    (net (code "100") (name "unconnected-(U$1-+3V3.2-Pad3V3.2)") (class "Default")
      (node (ref "U$1") (pin "3V3.2") (pinfunction "+3V3.2_3V3.2") (pintype "bidirectional"))
    )
    (net (code "101") (name "unconnected-(U$1-AREF-PadAREF.1)") (class "Default")
      (node (ref "U$1") (pin "AREF.1") (pinfunction "AREF_AREF.1") (pintype "bidirectional"))
    )
    (net (code "102") (name "unconnected-(U$1-PadA0)") (class "Default")
      (node (ref "U$1") (pin "A0") (pinfunction "A0_A0") (pintype "bidirectional"))
    )
    (net (code "103") (name "unconnected-(U$1-PadA1)") (class "Default")
      (node (ref "U$1") (pin "A1") (pinfunction "A1_A1") (pintype "bidirectional"))
    )
    (net (code "104") (name "unconnected-(U$1-PadA2)") (class "Default")
      (node (ref "U$1") (pin "A2") (pinfunction "A2_A2") (pintype "bidirectional"))
    )
    (net (code "105") (name "unconnected-(U$1-PadA3)") (class "Default")
      (node (ref "U$1") (pin "A3") (pinfunction "A3_A3") (pintype "bidirectional"))
    )
    (net (code "106") (name "unconnected-(U$1-PadA4)") (class "Default")
      (node (ref "U$1") (pin "A4") (pinfunction "A4_A4") (pintype "bidirectional"))
    )
    (net (code "107") (name "unconnected-(U$1-PadA5)") (class "Default")
      (node (ref "U$1") (pin "A5") (pinfunction "A5_A5") (pintype "bidirectional"))
    )
    (net (code "108") (name "unconnected-(U$1-PadA6)") (class "Default")
      (node (ref "U$1") (pin "A6") (pinfunction "A6_A6") (pintype "bidirectional"))
    )
    (net (code "109") (name "unconnected-(U$1-PadA7)") (class "Default")
      (node (ref "U$1") (pin "A7") (pinfunction "A7_A7") (pintype "bidirectional"))
    )
    (net (code "110") (name "unconnected-(U$1-PadA8)") (class "Default")
      (node (ref "U$1") (pin "A8") (pinfunction "A8_A8") (pintype "bidirectional"))
    )
    (net (code "111") (name "unconnected-(U$1-PadA9)") (class "Default")
      (node (ref "U$1") (pin "A9") (pinfunction "A9_A9") (pintype "bidirectional"))
    )
    (net (code "112") (name "unconnected-(U$1-PadA10)") (class "Default")
      (node (ref "U$1") (pin "A10") (pinfunction "A10_A10") (pintype "bidirectional"))
    )
    (net (code "113") (name "unconnected-(U$1-PadA11)") (class "Default")
      (node (ref "U$1") (pin "A11") (pinfunction "A11_A11") (pintype "bidirectional"))
    )
    (net (code "114") (name "unconnected-(U$1-PadA12)") (class "Default")
      (node (ref "U$1") (pin "A12") (pinfunction "A12_A12") (pintype "bidirectional"))
    )
    (net (code "115") (name "unconnected-(U$1-PadA13)") (class "Default")
      (node (ref "U$1") (pin "A13") (pinfunction "A13_A13") (pintype "bidirectional"))
    )
    (net (code "116") (name "unconnected-(U$1-PadD13)") (class "Default")
      (node (ref "U$1") (pin "D13") (pinfunction "D13_D13") (pintype "bidirectional"))
    )
    (net (code "117") (name "unconnected-(U$1-PadD18)") (class "Default")
      (node (ref "U$1") (pin "D18") (pinfunction "D18_D18") (pintype "bidirectional"))
    )
    (net (code "118") (name "unconnected-(U$1-PadD19)") (class "Default")
      (node (ref "U$1") (pin "D19") (pinfunction "D19_D19") (pintype "bidirectional"))
    )
    (net (code "119") (name "unconnected-(U$1-PadRST)") (class "Default")
      (node (ref "U$1") (pin "RST") (pinfunction "RST_RST") (pintype "bidirectional"))
    )
    (net (code "120") (name "unconnected-(U$1-PadRX)") (class "Default")
      (node (ref "U$1") (pin "RX") (pinfunction "RX_RX") (pintype "bidirectional"))
    )
    (net (code "121") (name "unconnected-(U$1-PadTX)") (class "Default")
      (node (ref "U$1") (pin "TX") (pinfunction "TX_TX") (pintype "bidirectional"))
    )
    (net (code "122") (name "unconnected-(U$1-PadVIN.1)") (class "Default")
      (node (ref "U$1") (pin "VIN.1") (pinfunction "VIN.1_VIN.1") (pintype "bidirectional"))
    )
    (net (code "123") (name "unconnected-(U$1-PadVIN.2)") (class "Default")
      (node (ref "U$1") (pin "VIN.2") (pinfunction "VIN.2_VIN.2") (pintype "bidirectional"))
    )
    (net (code "124") (name "unconnected-(U$2-P$1-Pad3V0)") (class "Default")
      (node (ref "U$2") (pin "3V0") (pinfunction "P$1_3V0") (pintype "bidirectional"))
    )
    (net (code "125") (name "unconnected-(U$2-P$2-PadADR)") (class "Default")
      (node (ref "U$2") (pin "ADR") (pinfunction "P$2_ADR") (pintype "bidirectional"))
    )
    (net (code "126") (name "unconnected-(U$2-P$4-PadINT)") (class "Default")
      (node (ref "U$2") (pin "INT") (pinfunction "P$4_INT") (pintype "bidirectional"))
    )
    (net (code "127") (name "unconnected-(U$2-P$5-PadPS0)") (class "Default")
      (node (ref "U$2") (pin "PS0") (pinfunction "P$5_PS0") (pintype "bidirectional"))
    )
    (net (code "128") (name "unconnected-(U$2-P$6-PadPS1)") (class "Default")
      (node (ref "U$2") (pin "PS1") (pinfunction "P$6_PS1") (pintype "bidirectional"))
    )
    (net (code "129") (name "unconnected-(U$2-P$7-PadRST)") (class "Default")
      (node (ref "U$2") (pin "RST") (pinfunction "P$7_RST") (pintype "bidirectional"))
    )
  )
)
